# EIS_Flow_Main.net
KiCad netlist of a schematic drawn in Altium Designer
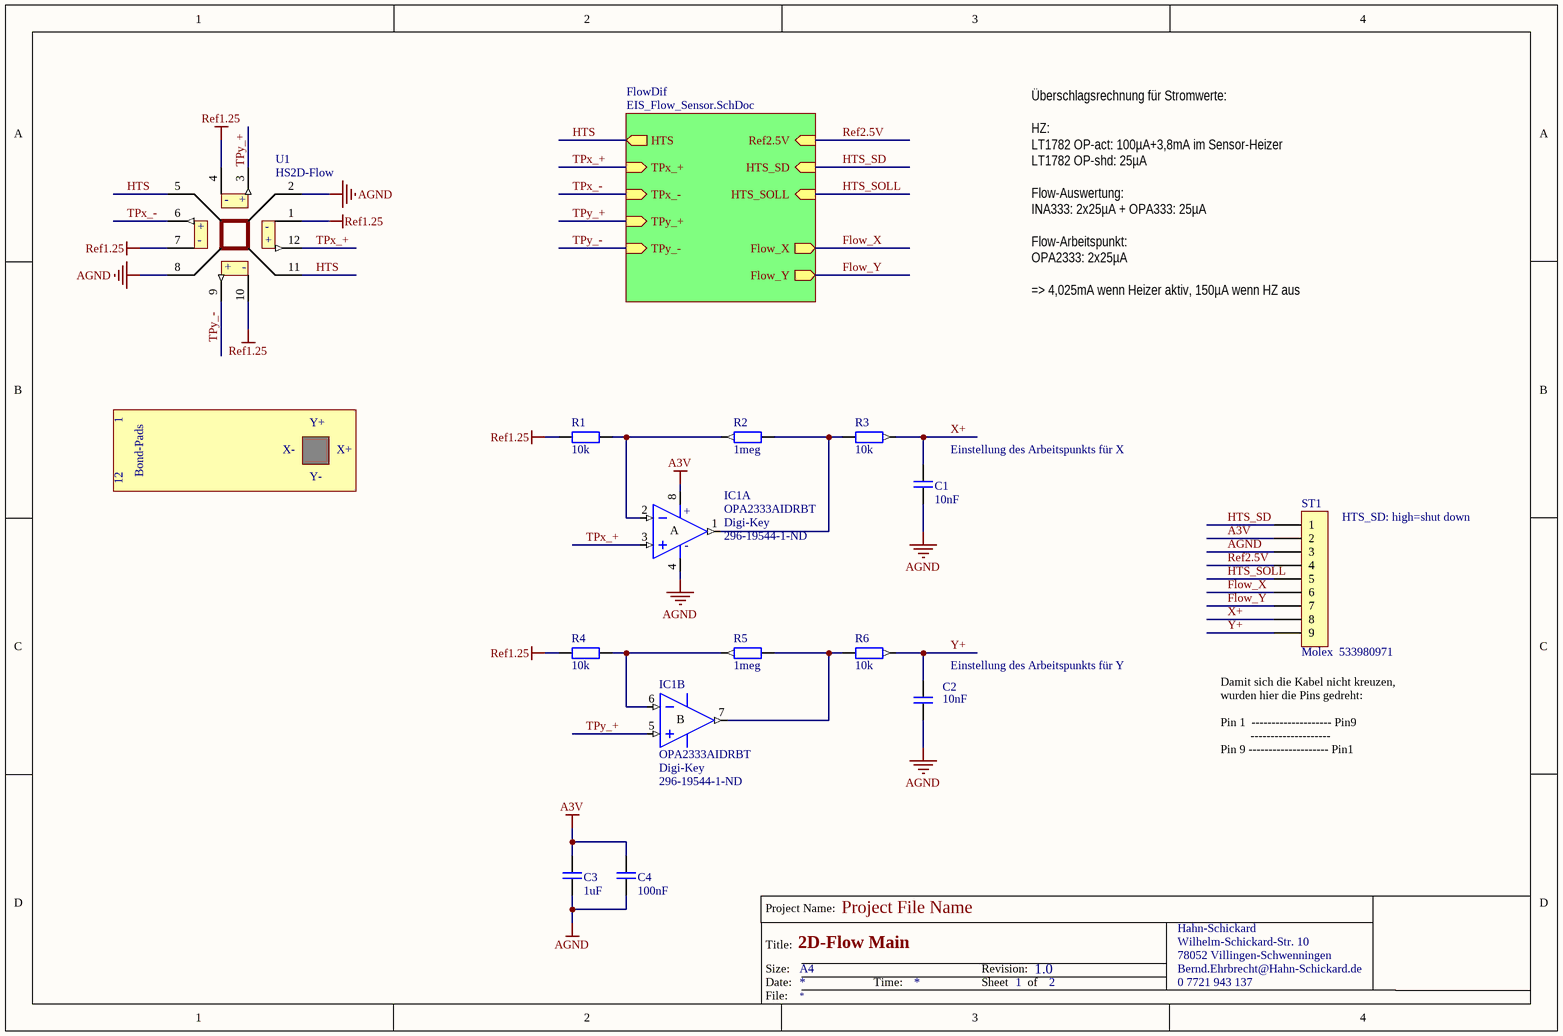
[diagram p0: EIS_Flow_Main.SchDoc]

(export (version "E")
  (design (tool "Eeschema 10.0.6"))
  (components
    (comp (ref "C1")
      (value "10nF")
      (footprint "CAPC1608N")
      (libsource (lib "My_Schlib_6_28") (part "Kondensator SMD Keramik"))
    )
    (comp (ref "C2")
      (value "10nF")
      (footprint "CAPC1608N")
      (libsource (lib "My_Schlib_6_28") (part "Kondensator SMD Keramik"))
    )
    (comp (ref "C3")
      (value "1uF")
      (footprint "CAPC2012N")
      (libsource (lib "My_Schlib_6_18") (part "Kondensator SMD Keramik"))
    )
    (comp (ref "C4")
      (value "100nF")
      (footprint "CAPC1608N")
      (libsource (lib "My_Schlib_6_28") (part "Kondensator SMD Keramik"))
    )
    (comp (ref "IC1")
      (value "OPA2333AIDRBT")
      (footprint "TI DRB (S-PVON-N8)")
      (description "Dual micro Power OP")
      (fields
        (field (name "SUPPLIER 1") "Digi-Key")
        (field (name "SUPPLIER PART NUMBER 1") "296-19544-1-ND")
        (field (name "09_ERSTELLER") "HSG Jürgen Merz")
      )
      (libsource (lib "My_Schlib_6_27") (part "OPA2333AIDRBT"))
    )
    (comp (ref "R1")
      (value "10k")
      (footprint "RESC1608N")
      (libsource (lib "My_Schlib_6_28") (part "Widerstand SMD"))
    )
    (comp (ref "R2")
      (value "1meg")
      (footprint "RESC1608N")
      (libsource (lib "My_Schlib_6_28") (part "Widerstand SMD"))
    )
    (comp (ref "R3")
      (value "10k")
      (footprint "RESC1608N")
      (libsource (lib "My_Schlib_6_28") (part "Widerstand SMD"))
    )
    (comp (ref "R4")
      (value "10k")
      (footprint "RESC1608N")
      (libsource (lib "My_Schlib_6_28") (part "Widerstand SMD"))
    )
    (comp (ref "R5")
      (value "1meg")
      (footprint "RESC1608N")
      (libsource (lib "My_Schlib_6_28") (part "Widerstand SMD"))
    )
    (comp (ref "R6")
      (value "10k")
      (footprint "RESC1608N")
      (libsource (lib "My_Schlib_6_28") (part "Widerstand SMD"))
    )
    (comp (ref "ST1")
      (value "Molex  533980971")
      (footprint "Picoblade 9*1,25V")
      (libsource (lib "My_Schlib_6_28") (part "MOLEX_Picoblade_9V"))
    )
    (comp (ref "U1")
      (value "HS2D-Flow")
      (footprint "Bond_Flow_12p")
      (description "2d Strömungssensor Hahn-Schickard")
      (libsource (lib "Eis_Lib") (part "HS2D-Flow"))
    )
  )
  (nets
    (net (code "1") (name "/Flow_X") (class "Default")
      (node (ref "ST1") (pin "6") (pinfunction "6_6") (pintype "passive"))
    )
    (net (code "2") (name "/Flow_Y") (class "Default")
      (node (ref "ST1") (pin "7") (pinfunction "7_7") (pintype "passive"))
    )
    (net (code "3") (name "/HTS") (class "Default")
      (node (ref "U1") (pin "11") (pinfunction "HZ_no_11") (pintype "passive"))
      (node (ref "U1") (pin "5") (pinfunction "HZ_sw_5") (pintype "passive"))
    )
    (net (code "4") (name "/HTS_SD") (class "Default")
      (node (ref "ST1") (pin "1") (pinfunction "1_1") (pintype "passive"))
    )
    (net (code "5") (name "/HTS_SOLL") (class "Default")
      (node (ref "ST1") (pin "5") (pinfunction "5_5") (pintype "passive"))
    )
    (net (code "6") (name "/Ref2.5V") (class "Default")
      (node (ref "ST1") (pin "4") (pinfunction "4_4") (pintype "passive"))
    )
    (net (code "7") (name "/TPx_+") (class "Default")
      (node (ref "IC1") (pin "3") (pinfunction "IN1+_3") (pintype "input"))
      (node (ref "U1") (pin "12") (pinfunction "TPn+_12") (pintype "output"))
    )
    (net (code "8") (name "/TPx_-") (class "Default")
      (node (ref "U1") (pin "6") (pinfunction "TPs+_6") (pintype "output"))
    )
    (net (code "9") (name "/TPy_+") (class "Default")
      (node (ref "IC1") (pin "5") (pinfunction "IN1+_5") (pintype "input"))
      (node (ref "U1") (pin "3") (pinfunction "TPw+_3") (pintype "output"))
    )
    (net (code "10") (name "/TPy_-") (class "Default")
      (node (ref "U1") (pin "9") (pinfunction "TPo+_9") (pintype "output"))
    )
    (net (code "11") (name "/X+") (class "Default")
      (node (ref "C1") (pin "2") (pinfunction "2_2") (pintype "passive"))
      (node (ref "R3") (pin "2") (pinfunction "2_2") (pintype "passive"))
      (node (ref "ST1") (pin "8") (pinfunction "8_8") (pintype "passive"))
    )
    (net (code "12") (name "/Y+") (class "Default")
      (node (ref "C2") (pin "1") (pinfunction "1_1") (pintype "passive"))
      (node (ref "R6") (pin "2") (pinfunction "2_2") (pintype "passive"))
      (node (ref "ST1") (pin "9") (pinfunction "9_9") (pintype "passive"))
    )
    (net (code "13") (name "A3V") (class "Default")
      (node (ref "C3") (pin "1") (pinfunction "1_1") (pintype "passive"))
      (node (ref "C4") (pin "1") (pinfunction "1_1") (pintype "passive"))
      (node (ref "IC1") (pin "8") (pinfunction "V+_8") (pintype "power_in"))
      (node (ref "ST1") (pin "2") (pinfunction "2_2") (pintype "passive"))
    )
    (net (code "14") (name "AGND") (class "Default")
      (node (ref "C1") (pin "1") (pinfunction "1_1") (pintype "passive"))
      (node (ref "C2") (pin "2") (pinfunction "2_2") (pintype "passive"))
      (node (ref "C3") (pin "2") (pinfunction "2_2") (pintype "passive"))
      (node (ref "C4") (pin "2") (pinfunction "2_2") (pintype "passive"))
      (node (ref "IC1") (pin "4") (pinfunction "V-_4") (pintype "power_in"))
      (node (ref "ST1") (pin "3") (pinfunction "3_3") (pintype "passive"))
      (node (ref "U1") (pin "2") (pinfunction "HZ_nw_2") (pintype "passive"))
      (node (ref "U1") (pin "8") (pinfunction "HZ_so_8") (pintype "passive"))
    )
    (net (code "15") (name "Net-(IC1A-IN1-)") (class "Default")
      (node (ref "IC1") (pin "2") (pinfunction "IN1-_2") (pintype "input"))
      (node (ref "R1") (pin "2") (pinfunction "2_2") (pintype "passive"))
      (node (ref "R2") (pin "1") (pinfunction "1_1") (pintype "passive"))
    )
    (net (code "16") (name "Net-(IC1A-OUT1)") (class "Default")
      (node (ref "IC1") (pin "1") (pinfunction "OUT1_1") (pintype "output"))
      (node (ref "R2") (pin "2") (pinfunction "2_2") (pintype "passive"))
      (node (ref "R3") (pin "1") (pinfunction "1_1") (pintype "passive"))
    )
    (net (code "17") (name "Net-(IC1B-IN1-)") (class "Default")
      (node (ref "IC1") (pin "6") (pinfunction "IN1-_6") (pintype "input"))
      (node (ref "R4") (pin "2") (pinfunction "2_2") (pintype "passive"))
      (node (ref "R5") (pin "1") (pinfunction "1_1") (pintype "passive"))
    )
    (net (code "18") (name "Net-(IC1B-OUT1)") (class "Default")
      (node (ref "IC1") (pin "7") (pinfunction "OUT1_7") (pintype "output"))
      (node (ref "R5") (pin "2") (pinfunction "2_2") (pintype "passive"))
      (node (ref "R6") (pin "1") (pinfunction "1_1") (pintype "passive"))
    )
    (net (code "19") (name "Ref1.25") (class "Default")
      (node (ref "R1") (pin "1") (pinfunction "1_1") (pintype "passive"))
      (node (ref "R4") (pin "1") (pinfunction "1_1") (pintype "passive"))
      (node (ref "U1") (pin "1") (pinfunction "TPn-_1") (pintype "passive"))
      (node (ref "U1") (pin "10") (pinfunction "TPo-_10") (pintype "passive"))
      (node (ref "U1") (pin "4") (pinfunction "TPw-_4") (pintype "passive"))
      (node (ref "U1") (pin "7") (pinfunction "TPs-_7") (pintype "passive"))
    )
  )
)
